# board_schematic_v2.net
KiCad netlist of a schematic drawn in EAGLE
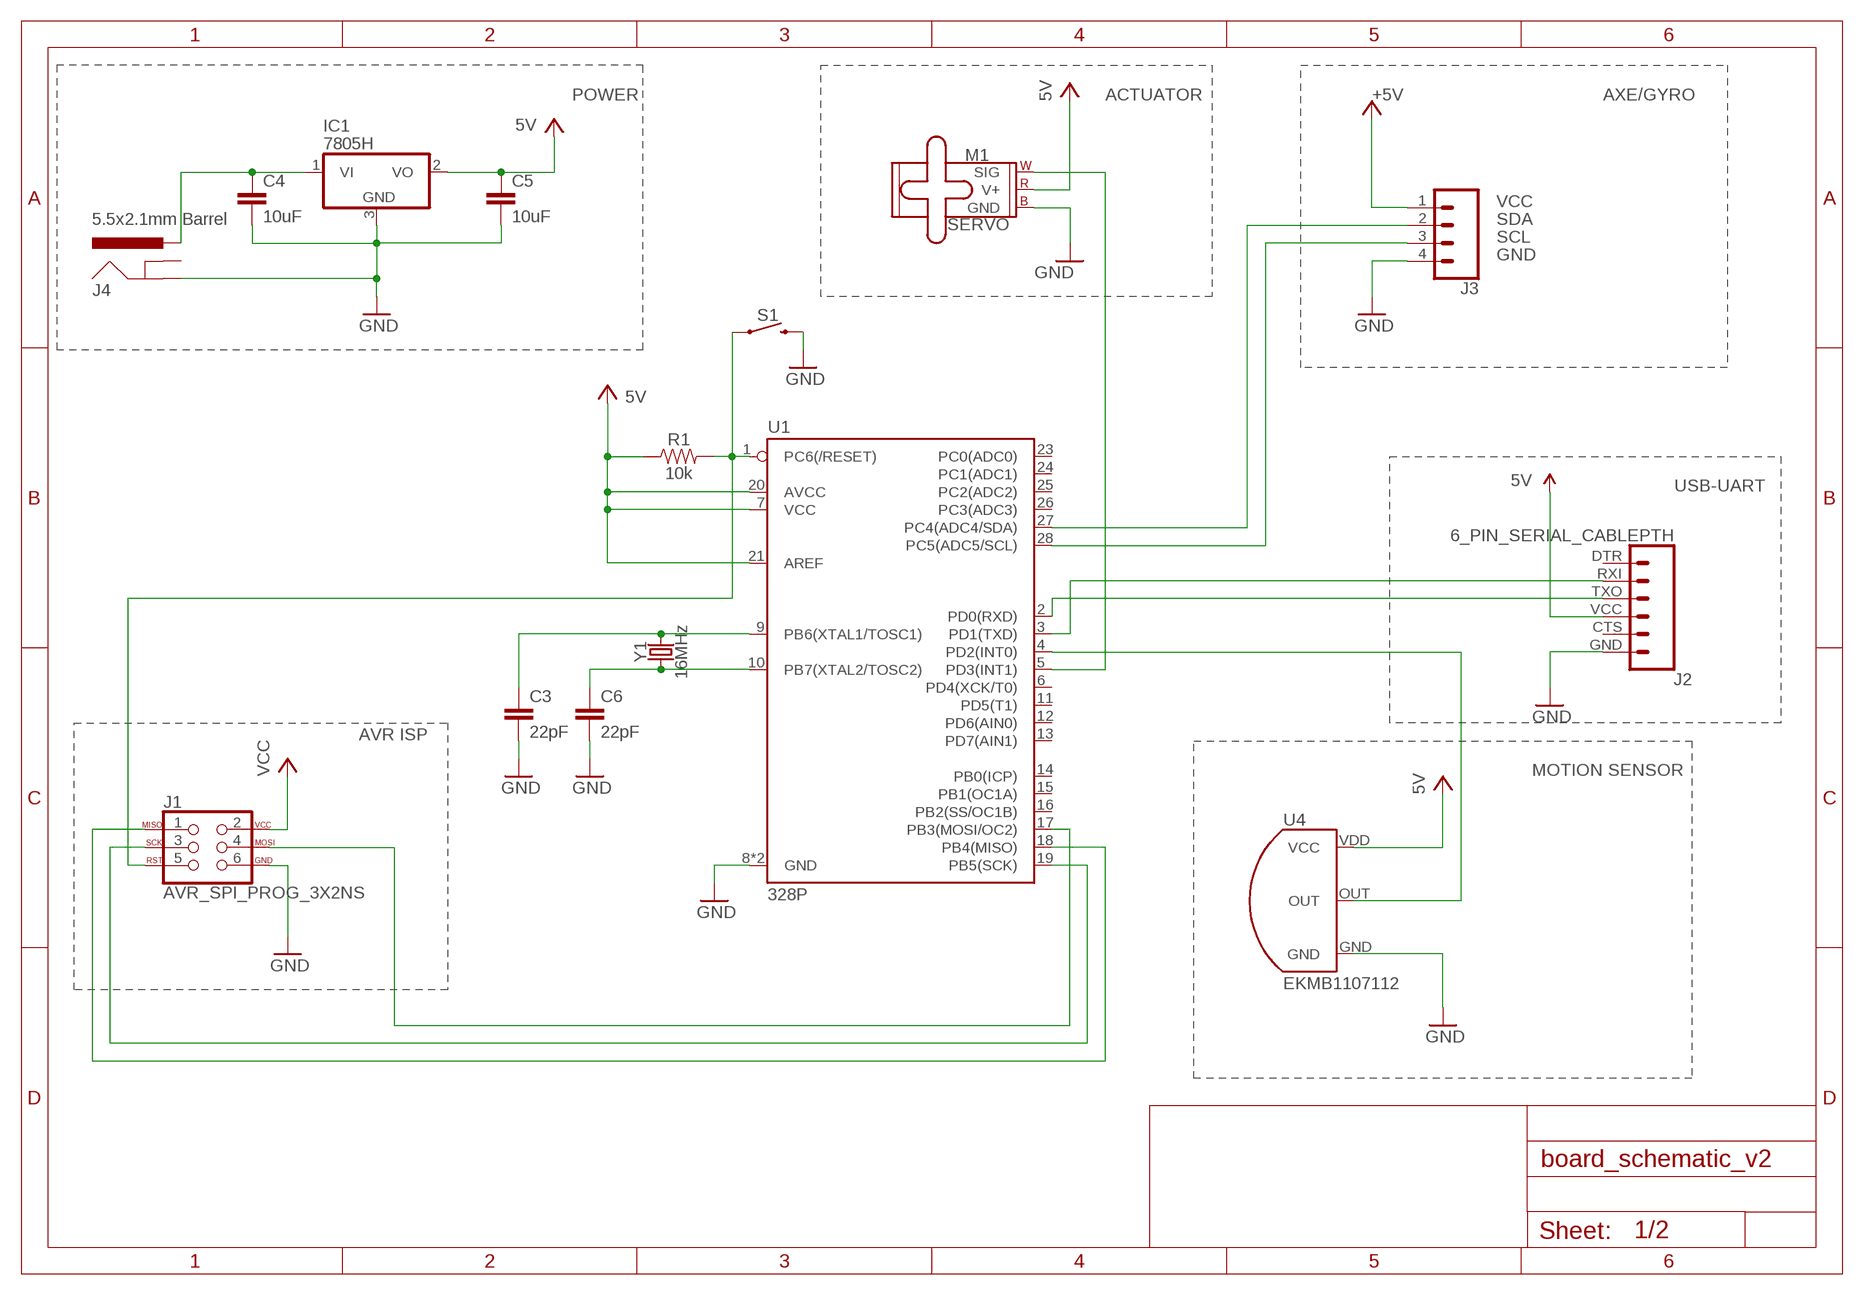
[diagram p0: schematic, sheet 1]

(export (version "E")
  (design (tool "Eeschema 10.0.6"))
  (components
    (comp (ref "C3")
      (value "22pF")
      (footprint "eagle-import:0402-TIGHT")
      (libsource (lib "eagle-import") (part "22PF-0402T-16V-10%"))
    )
    (comp (ref "C4")
      (value "10uF")
      (footprint "eagle-import:0402-TIGHT")
      (libsource (lib "eagle-import") (part "10UF-0402T-6.3V-20%"))
    )
    (comp (ref "C5")
      (value "10uF")
      (footprint "eagle-import:0402-TIGHT")
      (libsource (lib "eagle-import") (part "10UF-0402T-6.3V-20%"))
    )
    (comp (ref "C6")
      (value "22pF")
      (footprint "eagle-import:0402-TIGHT")
      (libsource (lib "eagle-import") (part "22PF-0402T-16V-10%"))
    )
    (comp (ref "IC1")
      (value "7805H")
      (footprint "eagle-import:TO39")
      (libsource (lib "eagle-import") (part "78H05"))
    )
    (comp (ref "J1")
      (value "AVR_SPI_PROG_3X2NS")
      (footprint "eagle-import:2X3-NS")
      (libsource (lib "eagle-import") (part "AVR_SPI_PROG_3X2NS"))
    )
    (comp (ref "J2")
      (value "6_PIN_SERIAL_CABLEPTH")
      (footprint "eagle-import:FTDI_BASIC")
      (libsource (lib "eagle-import") (part "6_PIN_SERIAL_CABLEPTH"))
    )
    (comp (ref "J3")
      (value "CONN_04PTH")
      (footprint "eagle-import:1X04")
      (libsource (lib "eagle-import") (part "CONN_04PTH"))
    )
    (comp (ref "J4")
      (value "5.5x2.1mm Barrel")
      (footprint "eagle-import:POWER_JACK_SMD")
      (libsource (lib "eagle-import") (part "POWER_JACKSMD"))
    )
    (comp (ref "M1")
      (value "SERVO")
      (footprint "eagle-import:1X03")
      (libsource (lib "eagle-import") (part "SERVO"))
    )
    (comp (ref "R1")
      (value "10k")
      (footprint "eagle-import:0402")
      (libsource (lib "eagle-import") (part "10KOHM-0402-1/16W-1%"))
    )
    (comp (ref "S1")
      (value "MOMENTARY-SWITCH-SPST-PTH-6.0MM")
      (footprint "eagle-import:TACTILE_SWITCH_PTH_6.0MM")
      (libsource (lib "eagle-import") (part "MOMENTARY-SWITCH-SPST-PTH-6.0MM"))
    )
    (comp (ref "U1")
      (value "328P")
      (footprint "eagle-import:DIP28")
      (libsource (lib "eagle-import") (part "ATMEGA328P_PDIP"))
    )
    (comp (ref "U4")
      (value "EKMB1107112")
      (footprint "eagle-import:TO-3")
      (libsource (lib "eagle-import") (part "PIR_EKMB1107112"))
    )
    (comp (ref "Y1")
      (value "16MHz")
      (footprint "eagle-import:HC49US")
      (libsource (lib "eagle-import") (part "CRYSTAL-16MHZPTH-HC49US"))
    )
  )
  (nets
    (net (code "1") (name "GND") (class "Default")
      (node (ref "C3") (pin "2") (pinfunction "2_2") (pintype "passive"))
      (node (ref "C4") (pin "2") (pinfunction "2_2") (pintype "passive"))
      (node (ref "C5") (pin "2") (pinfunction "2_2") (pintype "passive"))
      (node (ref "C6") (pin "2") (pinfunction "2_2") (pintype "passive"))
      (node (ref "IC1") (pin "3") (pinfunction "GND_3") (pintype "passive"))
      (node (ref "J1") (pin "6") (pinfunction "6_6") (pintype "passive"))
      (node (ref "J2") (pin "GND") (pinfunction "6_GND") (pintype "passive"))
      (node (ref "J3") (pin "4") (pinfunction "4_4") (pintype "passive"))
      (node (ref "J4") (pin "P$4") (pinfunction "GND_P$4") (pintype "bidirectional"))
      (node (ref "M1") (pin "3") (pinfunction "GND_3") (pintype "bidirectional"))
      (node (ref "S1") (pin "3") (pinfunction "2_3") (pintype "passive"))
      (node (ref "U1") (pin "22") (pinfunction "GND_22") (pintype "bidirectional"))
      (node (ref "U1") (pin "8") (pinfunction "GND_8") (pintype "bidirectional"))
      (node (ref "U4") (pin "GND") (pinfunction "GND_GND") (pintype "bidirectional"))
    )
    (net (code "2") (name "Net-(IC1-VI)") (class "Default")
      (node (ref "C4") (pin "1") (pinfunction "1_1") (pintype "passive"))
      (node (ref "IC1") (pin "1") (pinfunction "VI_1") (pintype "input"))
      (node (ref "J4") (pin "VIN0") (pinfunction "PWR_VIN0") (pintype "bidirectional"))
    )
    (net (code "3") (name "Net-(J2-2)") (class "Default")
      (node (ref "J2") (pin "RXI") (pinfunction "2_RXI") (pintype "passive"))
      (node (ref "U1") (pin "3") (pinfunction "PD1(TXD)_3") (pintype "bidirectional"))
    )
    (net (code "4") (name "Net-(J2-3)") (class "Default")
      (node (ref "J2") (pin "TXO") (pinfunction "3_TXO") (pintype "passive"))
      (node (ref "U1") (pin "2") (pinfunction "PD0(RXD)_2") (pintype "bidirectional"))
    )
    (net (code "5") (name "Net-(M1-SIG)") (class "Default")
      (node (ref "M1") (pin "1") (pinfunction "SIG_1") (pintype "bidirectional"))
      (node (ref "U1") (pin "5") (pinfunction "PD3(INT1)_5") (pintype "bidirectional"))
    )
    (net (code "6") (name "Net-(U1-PB3(MOSI{slash}OC2))") (class "Default")
      (node (ref "J1") (pin "4") (pinfunction "4_4") (pintype "passive"))
      (node (ref "U1") (pin "17") (pinfunction "PB3(MOSI/OC2)_17") (pintype "bidirectional"))
    )
    (net (code "7") (name "Net-(U1-PB4(MISO))") (class "Default")
      (node (ref "J1") (pin "1") (pinfunction "1_1") (pintype "passive"))
      (node (ref "U1") (pin "18") (pinfunction "PB4(MISO)_18") (pintype "bidirectional"))
    )
    (net (code "8") (name "Net-(U1-PB5(SCK))") (class "Default")
      (node (ref "J1") (pin "3") (pinfunction "3_3") (pintype "passive"))
      (node (ref "U1") (pin "19") (pinfunction "PB5(SCK)_19") (pintype "bidirectional"))
    )
    (net (code "9") (name "Net-(U1-PB6(XTAL1{slash}TOSC1))") (class "Default")
      (node (ref "C3") (pin "1") (pinfunction "1_1") (pintype "passive"))
      (node (ref "U1") (pin "9") (pinfunction "PB6(XTAL1/TOSC1)_9") (pintype "bidirectional"))
      (node (ref "Y1") (pin "2") (pinfunction "2_2") (pintype "passive"))
    )
    (net (code "10") (name "Net-(U1-PB7(XTAL2{slash}TOSC2))") (class "Default")
      (node (ref "C6") (pin "1") (pinfunction "1_1") (pintype "passive"))
      (node (ref "U1") (pin "10") (pinfunction "PB7(XTAL2/TOSC2)_10") (pintype "bidirectional"))
      (node (ref "Y1") (pin "1") (pinfunction "1_1") (pintype "passive"))
    )
    (net (code "11") (name "Net-(U1-PC4(ADC4{slash}SDA))") (class "Default")
      (node (ref "J3") (pin "2") (pinfunction "2_2") (pintype "passive"))
      (node (ref "U1") (pin "27") (pinfunction "PC4(ADC4/SDA)_27") (pintype "bidirectional"))
    )
    (net (code "12") (name "Net-(U1-PC5(ADC5{slash}SCL))") (class "Default")
      (node (ref "J3") (pin "3") (pinfunction "3_3") (pintype "passive"))
      (node (ref "U1") (pin "28") (pinfunction "PC5(ADC5/SCL)_28") (pintype "bidirectional"))
    )
    (net (code "13") (name "Net-(U1-PC6({slash}RESET))") (class "Default")
      (node (ref "J1") (pin "5") (pinfunction "5_5") (pintype "passive"))
      (node (ref "R1") (pin "2") (pinfunction "2_2") (pintype "passive"))
      (node (ref "S1") (pin "1") (pinfunction "1_1") (pintype "passive"))
      (node (ref "U1") (pin "1") (pinfunction "PC6(/RESET)_1") (pintype "bidirectional"))
    )
    (net (code "14") (name "Net-(U1-PD2(INT0))") (class "Default")
      (node (ref "U1") (pin "4") (pinfunction "PD2(INT0)_4") (pintype "bidirectional"))
      (node (ref "U4") (pin "OUT") (pinfunction "OUT_OUT") (pintype "bidirectional"))
    )
    (net (code "15") (name "VCC") (class "Default")
      (node (ref "C5") (pin "1") (pinfunction "1_1") (pintype "passive"))
      (node (ref "IC1") (pin "2") (pinfunction "VO_2") (pintype "passive"))
      (node (ref "J1") (pin "2") (pinfunction "2_2") (pintype "passive"))
      (node (ref "J2") (pin "VCC") (pinfunction "4_VCC") (pintype "passive"))
      (node (ref "J3") (pin "1") (pinfunction "1_1") (pintype "passive"))
      (node (ref "M1") (pin "2") (pinfunction "V+_2") (pintype "bidirectional"))
      (node (ref "R1") (pin "1") (pinfunction "1_1") (pintype "passive"))
      (node (ref "U1") (pin "20") (pinfunction "AVCC_20") (pintype "bidirectional"))
      (node (ref "U1") (pin "21") (pinfunction "AREF_21") (pintype "bidirectional"))
      (node (ref "U1") (pin "7") (pinfunction "VCC_7") (pintype "bidirectional"))
      (node (ref "U4") (pin "VDD") (pinfunction "VCC_VDD") (pintype "bidirectional"))
    )
    (net (code "16") (name "unconnected-(J2-1-PadDTR)") (class "Default")
      (node (ref "J2") (pin "DTR") (pinfunction "1_DTR") (pintype "passive"))
    )
    (net (code "17") (name "unconnected-(J2-5-PadCTS)") (class "Default")
      (node (ref "J2") (pin "CTS") (pinfunction "5_CTS") (pintype "passive"))
    )
    (net (code "18") (name "unconnected-(J4-GNDBREAK-PadGND)") (class "Default")
      (node (ref "J4") (pin "GND") (pinfunction "GNDBREAK_GND") (pintype "bidirectional"))
    )
    (net (code "19") (name "unconnected-(U1-PB0(ICP)-Pad14)") (class "Default")
      (node (ref "U1") (pin "14") (pinfunction "PB0(ICP)_14") (pintype "bidirectional"))
    )
    (net (code "20") (name "unconnected-(U1-PB1(OC1A)-Pad15)") (class "Default")
      (node (ref "U1") (pin "15") (pinfunction "PB1(OC1A)_15") (pintype "bidirectional"))
    )
    (net (code "21") (name "unconnected-(U1-PB2(SS{slash}OC1B)-Pad16)") (class "Default")
      (node (ref "U1") (pin "16") (pinfunction "PB2(SS/OC1B)_16") (pintype "bidirectional"))
    )
    (net (code "22") (name "unconnected-(U1-PC0(ADC0)-Pad23)") (class "Default")
      (node (ref "U1") (pin "23") (pinfunction "PC0(ADC0)_23") (pintype "bidirectional"))
    )
    (net (code "23") (name "unconnected-(U1-PC1(ADC1)-Pad24)") (class "Default")
      (node (ref "U1") (pin "24") (pinfunction "PC1(ADC1)_24") (pintype "bidirectional"))
    )
    (net (code "24") (name "unconnected-(U1-PC2(ADC2)-Pad25)") (class "Default")
      (node (ref "U1") (pin "25") (pinfunction "PC2(ADC2)_25") (pintype "bidirectional"))
    )
    (net (code "25") (name "unconnected-(U1-PC3(ADC3)-Pad26)") (class "Default")
      (node (ref "U1") (pin "26") (pinfunction "PC3(ADC3)_26") (pintype "bidirectional"))
    )
    (net (code "26") (name "unconnected-(U1-PD4(XCK{slash}T0)-Pad6)") (class "Default")
      (node (ref "U1") (pin "6") (pinfunction "PD4(XCK/T0)_6") (pintype "bidirectional"))
    )
    (net (code "27") (name "unconnected-(U1-PD5(T1)-Pad11)") (class "Default")
      (node (ref "U1") (pin "11") (pinfunction "PD5(T1)_11") (pintype "bidirectional"))
    )
    (net (code "28") (name "unconnected-(U1-PD6(AIN0)-Pad12)") (class "Default")
      (node (ref "U1") (pin "12") (pinfunction "PD6(AIN0)_12") (pintype "bidirectional"))
    )
    (net (code "29") (name "unconnected-(U1-PD7(AIN1)-Pad13)") (class "Default")
      (node (ref "U1") (pin "13") (pinfunction "PD7(AIN1)_13") (pintype "bidirectional"))
    )
  )
)
